# SensorDeCor.net
KiCad netlist of a schematic drawn in EAGLE
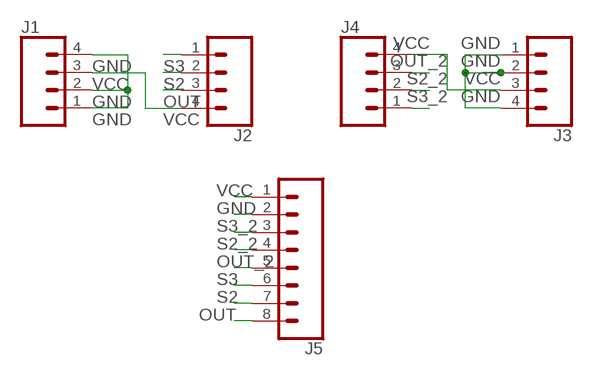
[diagram p0: schematic, sheet 1]

(export (version "E")
  (design (tool "Eeschema 10.0.6"))
  (components
    (comp (ref "J1")
      (value "CONN_04LONGPADS")
      (footprint "eagle-import:1X04_LONGPADS")
      (libsource (lib "eagle-import") (part "CONN_04LONGPADS"))
    )
    (comp (ref "J2")
      (value "CONN_04LONGPADS")
      (footprint "eagle-import:1X04_LONGPADS")
      (libsource (lib "eagle-import") (part "CONN_04LONGPADS"))
    )
    (comp (ref "J3")
      (value "CONN_04LONGPADS")
      (footprint "eagle-import:1X04_LONGPADS")
      (libsource (lib "eagle-import") (part "CONN_04LONGPADS"))
    )
    (comp (ref "J4")
      (value "CONN_04LONGPADS")
      (footprint "eagle-import:1X04_LONGPADS")
      (libsource (lib "eagle-import") (part "CONN_04LONGPADS"))
    )
    (comp (ref "J5")
      (value "CONN_08LONGPADS")
      (footprint "eagle-import:1X08_LONGPADS")
      (libsource (lib "eagle-import") (part "CONN_08LONGPADS"))
    )
  )
  (nets
    (net (code "1") (name "/GND") (class "Default")
      (node (ref "J1") (pin "1") (pinfunction "1_1") (pintype "passive"))
      (node (ref "J1") (pin "2") (pinfunction "2_2") (pintype "passive"))
      (node (ref "J1") (pin "4") (pinfunction "4_4") (pintype "passive"))
      (node (ref "J3") (pin "1") (pinfunction "1_1") (pintype "passive"))
      (node (ref "J3") (pin "2") (pinfunction "2_2") (pintype "passive"))
      (node (ref "J3") (pin "4") (pinfunction "4_4") (pintype "passive"))
      (node (ref "J5") (pin "2") (pinfunction "2_2") (pintype "passive"))
    )
    (net (code "2") (name "/OUT") (class "Default")
      (node (ref "J2") (pin "3") (pinfunction "3_3") (pintype "passive"))
      (node (ref "J5") (pin "8") (pinfunction "8_8") (pintype "passive"))
    )
    (net (code "3") (name "/OUT_2") (class "Default")
      (node (ref "J4") (pin "3") (pinfunction "3_3") (pintype "passive"))
      (node (ref "J5") (pin "5") (pinfunction "5_5") (pintype "passive"))
    )
    (net (code "4") (name "/S2") (class "Default")
      (node (ref "J2") (pin "2") (pinfunction "2_2") (pintype "passive"))
      (node (ref "J5") (pin "7") (pinfunction "7_7") (pintype "passive"))
    )
    (net (code "5") (name "/S2_2") (class "Default")
      (node (ref "J4") (pin "2") (pinfunction "2_2") (pintype "passive"))
      (node (ref "J5") (pin "4") (pinfunction "4_4") (pintype "passive"))
    )
    (net (code "6") (name "/S3") (class "Default")
      (node (ref "J2") (pin "1") (pinfunction "1_1") (pintype "passive"))
      (node (ref "J5") (pin "6") (pinfunction "6_6") (pintype "passive"))
    )
    (net (code "7") (name "/S3_2") (class "Default")
      (node (ref "J4") (pin "1") (pinfunction "1_1") (pintype "passive"))
      (node (ref "J5") (pin "3") (pinfunction "3_3") (pintype "passive"))
    )
    (net (code "8") (name "/VCC") (class "Default")
      (node (ref "J1") (pin "3") (pinfunction "3_3") (pintype "passive"))
      (node (ref "J2") (pin "4") (pinfunction "4_4") (pintype "passive"))
      (node (ref "J3") (pin "3") (pinfunction "3_3") (pintype "passive"))
      (node (ref "J4") (pin "4") (pinfunction "4_4") (pintype "passive"))
      (node (ref "J5") (pin "1") (pinfunction "1_1") (pintype "passive"))
    )
  )
)
